# 08_FPGA_banks_6_7_8.net
KiCad netlist of a schematic drawn in Altium Designer
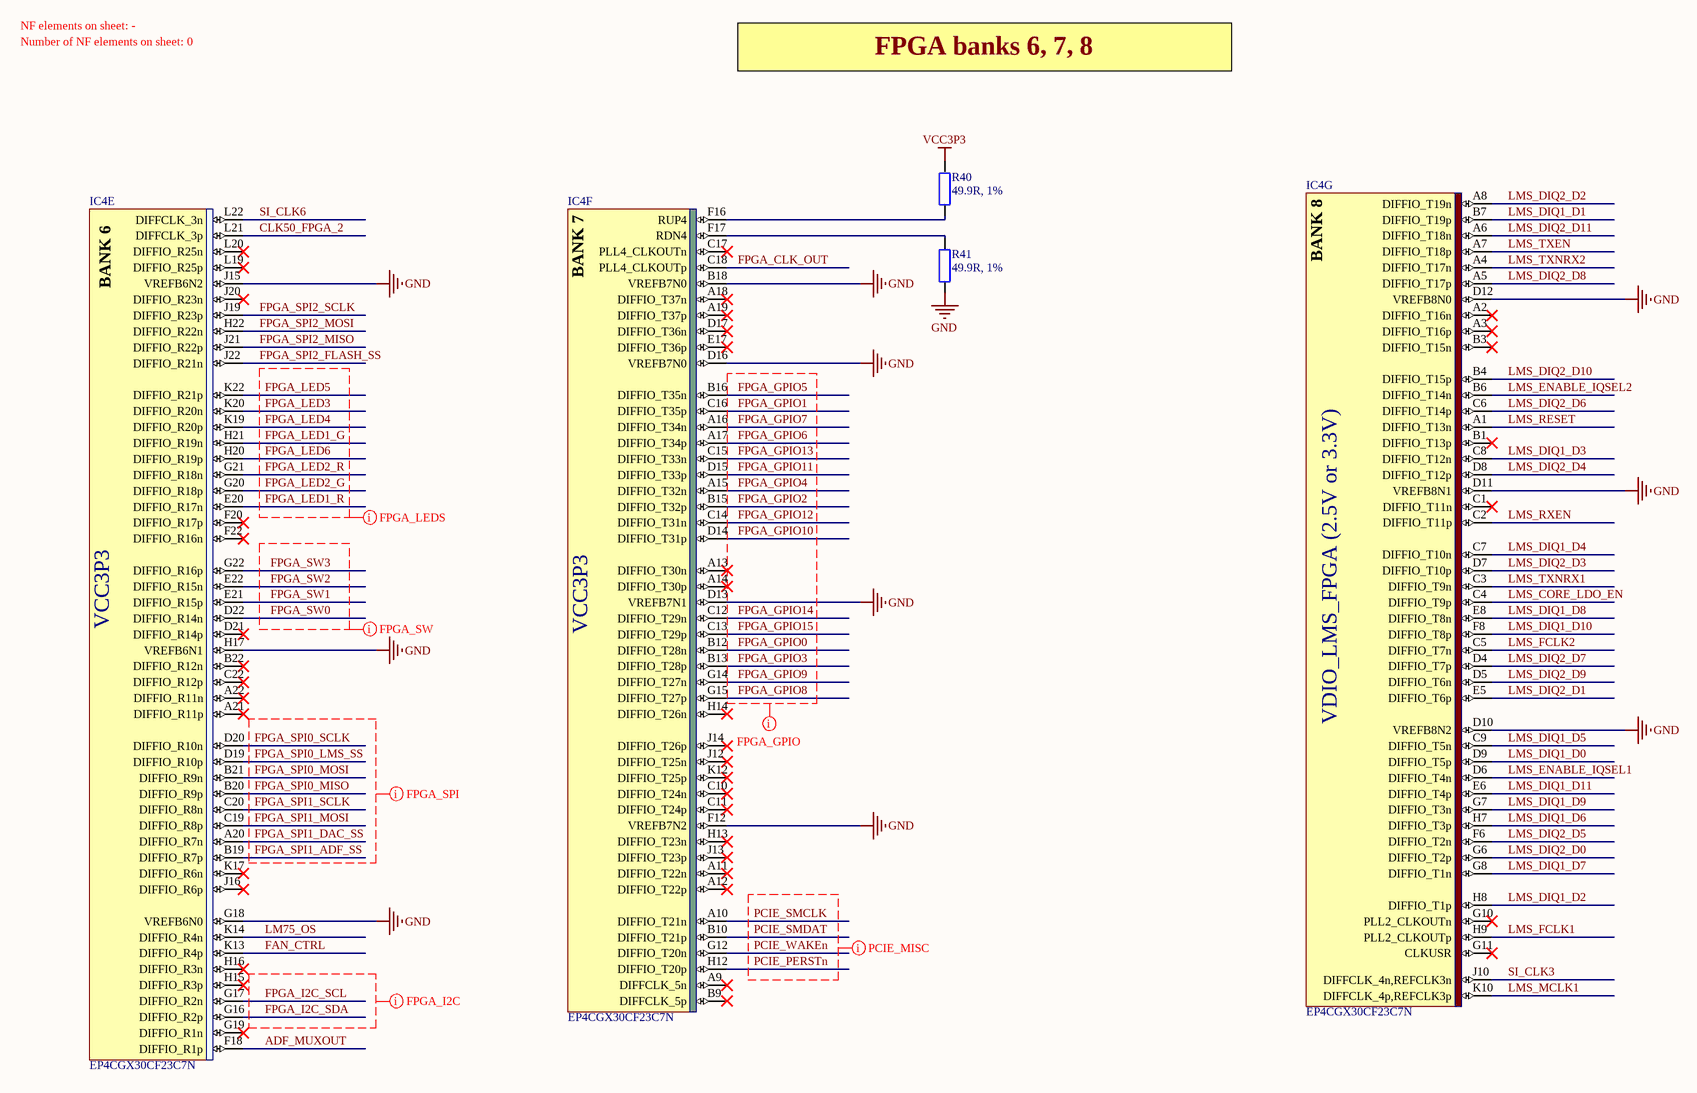
[diagram p0: 08_FPGA_banks_6_7_8.SchDoc]

(export (version "E")
  (design (tool "Eeschema 10.0.6"))
  (components
    (comp (ref "IC4")
      (value "EP4CGX30CF23C7N")
      (footprint "LimeMicroAltiumLib_pcbLib:ALTR-FBGA484_A-200")
      (fields (field (name "MANUFACTURER") "Altera"))
      (libsource (lib "LimeMicroAltiumLib_schLib") (part "EP4CGX30CF23C7N"))
    )
    (comp (ref "R40")
      (value "49.9R, 1%")
      (footprint "LimeMicroAltiumLib_pcbLib:RES0402")
      (fields
        (field (name "TOLERANCE") "±1%")
        (field (name "MANUFACTURER") "Samsung Electro-Mechanics America, Inc.")
        (field (name "MANUFACTURER PART NUMBER") "RC1005F49R9CS")
      )
      (libsource (lib "LimeMicroAltiumLib_schLib") (part "Res_0402"))
    )
    (comp (ref "R41")
      (value "49.9R, 1%")
      (footprint "LimeMicroAltiumLib_pcbLib:RES0402")
      (fields
        (field (name "TOLERANCE") "±1%")
        (field (name "MANUFACTURER") "Samsung Electro-Mechanics America, Inc.")
        (field (name "MANUFACTURER PART NUMBER") "RC1005F49R9CS")
      )
      (libsource (lib "LimeMicroAltiumLib_schLib") (part "Res_0402"))
    )
  )
  (nets
    (net (code "1") (name "/ADF_MUXOUT") (class "Default")
      (node (ref "IC4") (pin "F18") (pinfunction "DIFFIO_R1p_F18") (pintype "bidirectional"))
    )
    (net (code "2") (name "/CLK50_FPGA_2") (class "Default")
      (node (ref "IC4") (pin "L21") (pinfunction "DIFFCLK_3p_L21") (pintype "bidirectional"))
    )
    (net (code "3") (name "/FAN_CTRL") (class "Default")
      (node (ref "IC4") (pin "K13") (pinfunction "DIFFIO_R4p_K13") (pintype "bidirectional"))
    )
    (net (code "4") (name "/FPGA_CLK_OUT") (class "Default")
      (node (ref "IC4") (pin "C18") (pinfunction "PLL4_CLKOUTp_C18") (pintype "bidirectional"))
    )
    (net (code "5") (name "/FPGA_GPIO0") (class "Default")
      (node (ref "IC4") (pin "B12") (pinfunction "DIFFIO_T28n_B12") (pintype "bidirectional"))
    )
    (net (code "6") (name "/FPGA_GPIO1") (class "Default")
      (node (ref "IC4") (pin "C16") (pinfunction "DIFFIO_T35p_C16") (pintype "bidirectional"))
    )
    (net (code "7") (name "/FPGA_GPIO2") (class "Default")
      (node (ref "IC4") (pin "B15") (pinfunction "DIFFIO_T32p_B15") (pintype "bidirectional"))
    )
    (net (code "8") (name "/FPGA_GPIO3") (class "Default")
      (node (ref "IC4") (pin "B13") (pinfunction "DIFFIO_T28p_B13") (pintype "bidirectional"))
    )
    (net (code "9") (name "/FPGA_GPIO4") (class "Default")
      (node (ref "IC4") (pin "A15") (pinfunction "DIFFIO_T32n_A15") (pintype "bidirectional"))
    )
    (net (code "10") (name "/FPGA_GPIO5") (class "Default")
      (node (ref "IC4") (pin "B16") (pinfunction "DIFFIO_T35n_B16") (pintype "bidirectional"))
    )
    (net (code "11") (name "/FPGA_GPIO6") (class "Default")
      (node (ref "IC4") (pin "A17") (pinfunction "DIFFIO_T34p_A17") (pintype "bidirectional"))
    )
    (net (code "12") (name "/FPGA_GPIO7") (class "Default")
      (node (ref "IC4") (pin "A16") (pinfunction "DIFFIO_T34n_A16") (pintype "bidirectional"))
    )
    (net (code "13") (name "/FPGA_GPIO8") (class "Default")
      (node (ref "IC4") (pin "G15") (pinfunction "DIFFIO_T27p_G15") (pintype "bidirectional"))
    )
    (net (code "14") (name "/FPGA_GPIO9") (class "Default")
      (node (ref "IC4") (pin "G14") (pinfunction "DIFFIO_T27n_G14") (pintype "bidirectional"))
    )
    (net (code "15") (name "/FPGA_GPIO10") (class "Default")
      (node (ref "IC4") (pin "D14") (pinfunction "DIFFIO_T31p_D14") (pintype "bidirectional"))
    )
    (net (code "16") (name "/FPGA_GPIO11") (class "Default")
      (node (ref "IC4") (pin "D15") (pinfunction "DIFFIO_T33p_D15") (pintype "bidirectional"))
    )
    (net (code "17") (name "/FPGA_GPIO12") (class "Default")
      (node (ref "IC4") (pin "C14") (pinfunction "DIFFIO_T31n_C14") (pintype "bidirectional"))
    )
    (net (code "18") (name "/FPGA_GPIO13") (class "Default")
      (node (ref "IC4") (pin "C15") (pinfunction "DIFFIO_T33n_C15") (pintype "bidirectional"))
    )
    (net (code "19") (name "/FPGA_GPIO14") (class "Default")
      (node (ref "IC4") (pin "C12") (pinfunction "DIFFIO_T29n_C12") (pintype "bidirectional"))
    )
    (net (code "20") (name "/FPGA_GPIO15") (class "Default")
      (node (ref "IC4") (pin "C13") (pinfunction "DIFFIO_T29p_C13") (pintype "bidirectional"))
    )
    (net (code "21") (name "/FPGA_I2C_SCL") (class "Default")
      (node (ref "IC4") (pin "G17") (pinfunction "DIFFIO_R2n_G17") (pintype "bidirectional"))
    )
    (net (code "22") (name "/FPGA_I2C_SDA") (class "Default")
      (node (ref "IC4") (pin "G16") (pinfunction "DIFFIO_R2p_G16") (pintype "bidirectional"))
    )
    (net (code "23") (name "/FPGA_LED1_G") (class "Default")
      (node (ref "IC4") (pin "H21") (pinfunction "DIFFIO_R19n_H21") (pintype "bidirectional"))
    )
    (net (code "24") (name "/FPGA_LED1_R") (class "Default")
      (node (ref "IC4") (pin "E20") (pinfunction "DIFFIO_R17n_E20") (pintype "bidirectional"))
    )
    (net (code "25") (name "/FPGA_LED2_G") (class "Default")
      (node (ref "IC4") (pin "G20") (pinfunction "DIFFIO_R18p_G20") (pintype "bidirectional"))
    )
    (net (code "26") (name "/FPGA_LED2_R") (class "Default")
      (node (ref "IC4") (pin "G21") (pinfunction "DIFFIO_R18n_G21") (pintype "bidirectional"))
    )
    (net (code "27") (name "/FPGA_LED3") (class "Default")
      (node (ref "IC4") (pin "K20") (pinfunction "DIFFIO_R20n_K20") (pintype "bidirectional"))
    )
    (net (code "28") (name "/FPGA_LED4") (class "Default")
      (node (ref "IC4") (pin "K19") (pinfunction "DIFFIO_R20p_K19") (pintype "bidirectional"))
    )
    (net (code "29") (name "/FPGA_LED5") (class "Default")
      (node (ref "IC4") (pin "K22") (pinfunction "DIFFIO_R21p_K22") (pintype "bidirectional"))
    )
    (net (code "30") (name "/FPGA_LED6") (class "Default")
      (node (ref "IC4") (pin "H20") (pinfunction "DIFFIO_R19p_H20") (pintype "bidirectional"))
    )
    (net (code "31") (name "/FPGA_SPI0_LMS_SS") (class "Default")
      (node (ref "IC4") (pin "D19") (pinfunction "DIFFIO_R10p_D19") (pintype "bidirectional"))
    )
    (net (code "32") (name "/FPGA_SPI0_MISO") (class "Default")
      (node (ref "IC4") (pin "B20") (pinfunction "DIFFIO_R9p_B20") (pintype "bidirectional"))
    )
    (net (code "33") (name "/FPGA_SPI0_MOSI") (class "Default")
      (node (ref "IC4") (pin "B21") (pinfunction "DIFFIO_R9n_B21") (pintype "bidirectional"))
    )
    (net (code "34") (name "/FPGA_SPI0_SCLK") (class "Default")
      (node (ref "IC4") (pin "D20") (pinfunction "DIFFIO_R10n_D20") (pintype "bidirectional"))
    )
    (net (code "35") (name "/FPGA_SPI1_ADF_SS") (class "Default")
      (node (ref "IC4") (pin "B19") (pinfunction "DIFFIO_R7p_B19") (pintype "bidirectional"))
    )
    (net (code "36") (name "/FPGA_SPI1_DAC_SS") (class "Default")
      (node (ref "IC4") (pin "A20") (pinfunction "DIFFIO_R7n_A20") (pintype "bidirectional"))
    )
    (net (code "37") (name "/FPGA_SPI1_MOSI") (class "Default")
      (node (ref "IC4") (pin "C19") (pinfunction "DIFFIO_R8p_C19") (pintype "bidirectional"))
    )
    (net (code "38") (name "/FPGA_SPI1_SCLK") (class "Default")
      (node (ref "IC4") (pin "C20") (pinfunction "DIFFIO_R8n_C20") (pintype "bidirectional"))
    )
    (net (code "39") (name "/FPGA_SPI2_FLASH_SS") (class "Default")
      (node (ref "IC4") (pin "J22") (pinfunction "DIFFIO_R21n_J22") (pintype "bidirectional"))
    )
    (net (code "40") (name "/FPGA_SPI2_MISO") (class "Default")
      (node (ref "IC4") (pin "J21") (pinfunction "DIFFIO_R22p_J21") (pintype "bidirectional"))
    )
    (net (code "41") (name "/FPGA_SPI2_MOSI") (class "Default")
      (node (ref "IC4") (pin "H22") (pinfunction "DIFFIO_R22n_H22") (pintype "bidirectional"))
    )
    (net (code "42") (name "/FPGA_SPI2_SCLK") (class "Default")
      (node (ref "IC4") (pin "J19") (pinfunction "DIFFIO_R23p_J19") (pintype "bidirectional"))
    )
    (net (code "43") (name "/FPGA_SW0") (class "Default")
      (node (ref "IC4") (pin "D22") (pinfunction "DIFFIO_R14n_D22") (pintype "bidirectional"))
    )
    (net (code "44") (name "/FPGA_SW1") (class "Default")
      (node (ref "IC4") (pin "E21") (pinfunction "DIFFIO_R15p_E21") (pintype "bidirectional"))
    )
    (net (code "45") (name "/FPGA_SW2") (class "Default")
      (node (ref "IC4") (pin "E22") (pinfunction "DIFFIO_R15n_E22") (pintype "bidirectional"))
    )
    (net (code "46") (name "/FPGA_SW3") (class "Default")
      (node (ref "IC4") (pin "G22") (pinfunction "DIFFIO_R16p_G22") (pintype "bidirectional"))
    )
    (net (code "47") (name "/LM75_OS") (class "Default")
      (node (ref "IC4") (pin "K14") (pinfunction "DIFFIO_R4n_K14") (pintype "bidirectional"))
    )
    (net (code "48") (name "/LMS_CORE_LDO_EN") (class "Default")
      (node (ref "IC4") (pin "C4") (pinfunction "DIFFIO_T9p_C4") (pintype "bidirectional"))
    )
    (net (code "49") (name "/LMS_DIQ1_D0") (class "Default")
      (node (ref "IC4") (pin "D9") (pinfunction "DIFFIO_T5p_D9") (pintype "bidirectional"))
    )
    (net (code "50") (name "/LMS_DIQ1_D1") (class "Default")
      (node (ref "IC4") (pin "B7") (pinfunction "DIFFIO_T19p_B7") (pintype "bidirectional"))
    )
    (net (code "51") (name "/LMS_DIQ1_D2") (class "Default")
      (node (ref "IC4") (pin "H8") (pinfunction "DIFFIO_T1p_H8") (pintype "bidirectional"))
    )
    (net (code "52") (name "/LMS_DIQ1_D3") (class "Default")
      (node (ref "IC4") (pin "C8") (pinfunction "DIFFIO_T12n_C8") (pintype "bidirectional"))
    )
    (net (code "53") (name "/LMS_DIQ1_D4") (class "Default")
      (node (ref "IC4") (pin "C7") (pinfunction "DIFFIO_T10n_C7") (pintype "bidirectional"))
    )
    (net (code "54") (name "/LMS_DIQ1_D5") (class "Default")
      (node (ref "IC4") (pin "C9") (pinfunction "DIFFIO_T5n_C9") (pintype "bidirectional"))
    )
    (net (code "55") (name "/LMS_DIQ1_D6") (class "Default")
      (node (ref "IC4") (pin "H7") (pinfunction "DIFFIO_T3p_H7") (pintype "bidirectional"))
    )
    (net (code "56") (name "/LMS_DIQ1_D7") (class "Default")
      (node (ref "IC4") (pin "G8") (pinfunction "DIFFIO_T1n_G8") (pintype "bidirectional"))
    )
    (net (code "57") (name "/LMS_DIQ1_D8") (class "Default")
      (node (ref "IC4") (pin "E8") (pinfunction "DIFFIO_T8n_E8") (pintype "bidirectional"))
    )
    (net (code "58") (name "/LMS_DIQ1_D9") (class "Default")
      (node (ref "IC4") (pin "G7") (pinfunction "DIFFIO_T3n_G7") (pintype "bidirectional"))
    )
    (net (code "59") (name "/LMS_DIQ1_D10") (class "Default")
      (node (ref "IC4") (pin "F8") (pinfunction "DIFFIO_T8p_F8") (pintype "bidirectional"))
    )
    (net (code "60") (name "/LMS_DIQ1_D11") (class "Default")
      (node (ref "IC4") (pin "E6") (pinfunction "DIFFIO_T4p_E6") (pintype "bidirectional"))
    )
    (net (code "61") (name "/LMS_DIQ2_D0") (class "Default")
      (node (ref "IC4") (pin "G6") (pinfunction "DIFFIO_T2p_G6") (pintype "bidirectional"))
    )
    (net (code "62") (name "/LMS_DIQ2_D1") (class "Default")
      (node (ref "IC4") (pin "E5") (pinfunction "DIFFIO_T6p_E5") (pintype "bidirectional"))
    )
    (net (code "63") (name "/LMS_DIQ2_D2") (class "Default")
      (node (ref "IC4") (pin "A8") (pinfunction "DIFFIO_T19n_A8") (pintype "bidirectional"))
    )
    (net (code "64") (name "/LMS_DIQ2_D3") (class "Default")
      (node (ref "IC4") (pin "D7") (pinfunction "DIFFIO_T10p_D7") (pintype "bidirectional"))
    )
    (net (code "65") (name "/LMS_DIQ2_D4") (class "Default")
      (node (ref "IC4") (pin "D8") (pinfunction "DIFFIO_T12p_D8") (pintype "bidirectional"))
    )
    (net (code "66") (name "/LMS_DIQ2_D5") (class "Default")
      (node (ref "IC4") (pin "F6") (pinfunction "DIFFIO_T2n_F6") (pintype "bidirectional"))
    )
    (net (code "67") (name "/LMS_DIQ2_D6") (class "Default")
      (node (ref "IC4") (pin "C6") (pinfunction "DIFFIO_T14p_C6") (pintype "bidirectional"))
    )
    (net (code "68") (name "/LMS_DIQ2_D7") (class "Default")
      (node (ref "IC4") (pin "D4") (pinfunction "DIFFIO_T7p_D4") (pintype "bidirectional"))
    )
    (net (code "69") (name "/LMS_DIQ2_D8") (class "Default")
      (node (ref "IC4") (pin "A5") (pinfunction "DIFFIO_T17p_A5") (pintype "bidirectional"))
    )
    (net (code "70") (name "/LMS_DIQ2_D9") (class "Default")
      (node (ref "IC4") (pin "D5") (pinfunction "DIFFIO_T6n_D5") (pintype "bidirectional"))
    )
    (net (code "71") (name "/LMS_DIQ2_D10") (class "Default")
      (node (ref "IC4") (pin "B4") (pinfunction "DIFFIO_T15p_B4") (pintype "bidirectional"))
    )
    (net (code "72") (name "/LMS_DIQ2_D11") (class "Default")
      (node (ref "IC4") (pin "A6") (pinfunction "DIFFIO_T18n_A6") (pintype "bidirectional"))
    )
    (net (code "73") (name "/LMS_ENABLE_IQSEL1") (class "Default")
      (node (ref "IC4") (pin "D6") (pinfunction "DIFFIO_T4n_D6") (pintype "bidirectional"))
    )
    (net (code "74") (name "/LMS_ENABLE_IQSEL2") (class "Default")
      (node (ref "IC4") (pin "B6") (pinfunction "DIFFIO_T14n_B6") (pintype "bidirectional"))
    )
    (net (code "75") (name "/LMS_FCLK1") (class "Default")
      (node (ref "IC4") (pin "H9") (pinfunction "PLL2_CLKOUTp_H9") (pintype "bidirectional"))
    )
    (net (code "76") (name "/LMS_FCLK2") (class "Default")
      (node (ref "IC4") (pin "C5") (pinfunction "DIFFIO_T7n_C5") (pintype "bidirectional"))
    )
    (net (code "77") (name "/LMS_MCLK1") (class "Default")
      (node (ref "IC4") (pin "K10") (pinfunction "DIFFCLK_4p,REFCLK3p_K10") (pintype "bidirectional"))
    )
    (net (code "78") (name "/LMS_RESET") (class "Default")
      (node (ref "IC4") (pin "A1") (pinfunction "DIFFIO_T13n_A1") (pintype "bidirectional"))
    )
    (net (code "79") (name "/LMS_RXEN") (class "Default")
      (node (ref "IC4") (pin "C2") (pinfunction "DIFFIO_T11p_C2") (pintype "bidirectional"))
    )
    (net (code "80") (name "/LMS_TXEN") (class "Default")
      (node (ref "IC4") (pin "A7") (pinfunction "DIFFIO_T18p_A7") (pintype "bidirectional"))
    )
    (net (code "81") (name "/LMS_TXNRX1") (class "Default")
      (node (ref "IC4") (pin "C3") (pinfunction "DIFFIO_T9n_C3") (pintype "bidirectional"))
    )
    (net (code "82") (name "/LMS_TXNRX2") (class "Default")
      (node (ref "IC4") (pin "A4") (pinfunction "DIFFIO_T17n_A4") (pintype "bidirectional"))
    )
    (net (code "83") (name "/PCIE_PERSTn") (class "Default")
      (node (ref "IC4") (pin "H12") (pinfunction "DIFFIO_T20p_H12") (pintype "bidirectional"))
    )
    (net (code "84") (name "/PCIE_SMCLK") (class "Default")
      (node (ref "IC4") (pin "A10") (pinfunction "DIFFIO_T21n_A10") (pintype "bidirectional"))
    )
    (net (code "85") (name "/PCIE_SMDAT") (class "Default")
      (node (ref "IC4") (pin "B10") (pinfunction "DIFFIO_T21p_B10") (pintype "bidirectional"))
    )
    (net (code "86") (name "/PCIE_WAKEn") (class "Default")
      (node (ref "IC4") (pin "G12") (pinfunction "DIFFIO_T20n_G12") (pintype "bidirectional"))
    )
    (net (code "87") (name "/SI_CLK3") (class "Default")
      (node (ref "IC4") (pin "J10") (pinfunction "DIFFCLK_4n,REFCLK3n_J10") (pintype "bidirectional"))
    )
    (net (code "88") (name "/SI_CLK6") (class "Default")
      (node (ref "IC4") (pin "L22") (pinfunction "DIFFCLK_3n_L22") (pintype "bidirectional"))
    )
    (net (code "89") (name "GND") (class "Default")
      (node (ref "IC4") (pin "B18") (pinfunction "VREFB7N0_B18") (pintype "bidirectional"))
      (node (ref "IC4") (pin "D10") (pinfunction "VREFB8N2_D10") (pintype "bidirectional"))
      (node (ref "IC4") (pin "D11") (pinfunction "VREFB8N1_D11") (pintype "bidirectional"))
      (node (ref "IC4") (pin "D12") (pinfunction "VREFB8N0_D12") (pintype "bidirectional"))
      (node (ref "IC4") (pin "D13") (pinfunction "VREFB7N1_D13") (pintype "bidirectional"))
      (node (ref "IC4") (pin "D16") (pinfunction "VREFB7N0_D16") (pintype "bidirectional"))
      (node (ref "IC4") (pin "F12") (pinfunction "VREFB7N2_F12") (pintype "bidirectional"))
      (node (ref "IC4") (pin "G18") (pinfunction "VREFB6N0_G18") (pintype "bidirectional"))
      (node (ref "IC4") (pin "H17") (pinfunction "VREFB6N1_H17") (pintype "bidirectional"))
      (node (ref "IC4") (pin "J15") (pinfunction "VREFB6N2_J15") (pintype "bidirectional"))
      (node (ref "R41") (pin "1") (pinfunction "1_1") (pintype "passive"))
    )
    (net (code "90") (name "Net-(IC4F-RDN4)") (class "Default")
      (node (ref "IC4") (pin "F17") (pinfunction "RDN4_F17") (pintype "bidirectional"))
      (node (ref "R41") (pin "2") (pinfunction "2_2") (pintype "passive"))
    )
    (net (code "91") (name "Net-(IC4F-RUP4)") (class "Default")
      (node (ref "IC4") (pin "F16") (pinfunction "RUP4_F16") (pintype "bidirectional"))
      (node (ref "R40") (pin "1") (pinfunction "1_1") (pintype "passive"))
    )
    (net (code "92") (name "VCC3P3") (class "Default")
      (node (ref "R40") (pin "2") (pinfunction "2_2") (pintype "passive"))
    )
    (net (code "93") (name "unconnected-(IC4E-DIFFIO_R1n-PadG19)") (class "Default")
      (node (ref "IC4") (pin "G19") (pinfunction "DIFFIO_R1n_G19") (pintype "bidirectional+no_connect"))
    )
    (net (code "94") (name "unconnected-(IC4E-DIFFIO_R3n-PadH16)") (class "Default")
      (node (ref "IC4") (pin "H16") (pinfunction "DIFFIO_R3n_H16") (pintype "bidirectional+no_connect"))
    )
    (net (code "95") (name "unconnected-(IC4E-DIFFIO_R3p-PadH15)") (class "Default")
      (node (ref "IC4") (pin "H15") (pinfunction "DIFFIO_R3p_H15") (pintype "bidirectional+no_connect"))
    )
    (net (code "96") (name "unconnected-(IC4E-DIFFIO_R6n-PadK17)") (class "Default")
      (node (ref "IC4") (pin "K17") (pinfunction "DIFFIO_R6n_K17") (pintype "bidirectional+no_connect"))
    )
    (net (code "97") (name "unconnected-(IC4E-DIFFIO_R6p-PadJ16)") (class "Default")
      (node (ref "IC4") (pin "J16") (pinfunction "DIFFIO_R6p_J16") (pintype "bidirectional+no_connect"))
    )
    (net (code "98") (name "unconnected-(IC4E-DIFFIO_R11n-PadA22)") (class "Default")
      (node (ref "IC4") (pin "A22") (pinfunction "DIFFIO_R11n_A22") (pintype "bidirectional+no_connect"))
    )
    (net (code "99") (name "unconnected-(IC4E-DIFFIO_R11p-PadA21)") (class "Default")
      (node (ref "IC4") (pin "A21") (pinfunction "DIFFIO_R11p_A21") (pintype "bidirectional+no_connect"))
    )
    (net (code "100") (name "unconnected-(IC4E-DIFFIO_R12n-PadB22)") (class "Default")
      (node (ref "IC4") (pin "B22") (pinfunction "DIFFIO_R12n_B22") (pintype "bidirectional+no_connect"))
    )
    (net (code "101") (name "unconnected-(IC4E-DIFFIO_R12p-PadC22)") (class "Default")
      (node (ref "IC4") (pin "C22") (pinfunction "DIFFIO_R12p_C22") (pintype "bidirectional+no_connect"))
    )
    (net (code "102") (name "unconnected-(IC4E-DIFFIO_R14p-PadD21)") (class "Default")
      (node (ref "IC4") (pin "D21") (pinfunction "DIFFIO_R14p_D21") (pintype "bidirectional+no_connect"))
    )
    (net (code "103") (name "unconnected-(IC4E-DIFFIO_R16n-PadF22)") (class "Default")
      (node (ref "IC4") (pin "F22") (pinfunction "DIFFIO_R16n_F22") (pintype "bidirectional+no_connect"))
    )
    (net (code "104") (name "unconnected-(IC4E-DIFFIO_R17p-PadF20)") (class "Default")
      (node (ref "IC4") (pin "F20") (pinfunction "DIFFIO_R17p_F20") (pintype "bidirectional+no_connect"))
    )
    (net (code "105") (name "unconnected-(IC4E-DIFFIO_R23n-PadJ20)") (class "Default")
      (node (ref "IC4") (pin "J20") (pinfunction "DIFFIO_R23n_J20") (pintype "bidirectional+no_connect"))
    )
    (net (code "106") (name "unconnected-(IC4E-DIFFIO_R25n-PadL20)") (class "Default")
      (node (ref "IC4") (pin "L20") (pinfunction "DIFFIO_R25n_L20") (pintype "bidirectional+no_connect"))
    )
    (net (code "107") (name "unconnected-(IC4E-DIFFIO_R25p-PadL19)") (class "Default")
      (node (ref "IC4") (pin "L19") (pinfunction "DIFFIO_R25p_L19") (pintype "bidirectional+no_connect"))
    )
    (net (code "108") (name "unconnected-(IC4F-DIFFCLK_5n-PadA9)") (class "Default")
      (node (ref "IC4") (pin "A9") (pinfunction "DIFFCLK_5n_A9") (pintype "bidirectional+no_connect"))
    )
    (net (code "109") (name "unconnected-(IC4F-DIFFCLK_5p-PadB9)") (class "Default")
      (node (ref "IC4") (pin "B9") (pinfunction "DIFFCLK_5p_B9") (pintype "bidirectional+no_connect"))
    )
    (net (code "110") (name "unconnected-(IC4F-DIFFIO_T22n-PadA11)") (class "Default")
      (node (ref "IC4") (pin "A11") (pinfunction "DIFFIO_T22n_A11") (pintype "bidirectional+no_connect"))
    )
    (net (code "111") (name "unconnected-(IC4F-DIFFIO_T22p-PadA12)") (class "Default")
      (node (ref "IC4") (pin "A12") (pinfunction "DIFFIO_T22p_A12") (pintype "bidirectional+no_connect"))
    )
    (net (code "112") (name "unconnected-(IC4F-DIFFIO_T23n-PadH13)") (class "Default")
      (node (ref "IC4") (pin "H13") (pinfunction "DIFFIO_T23n_H13") (pintype "bidirectional+no_connect"))
    )
    (net (code "113") (name "unconnected-(IC4F-DIFFIO_T23p-PadJ13)") (class "Default")
      (node (ref "IC4") (pin "J13") (pinfunction "DIFFIO_T23p_J13") (pintype "bidirectional+no_connect"))
    )
    (net (code "114") (name "unconnected-(IC4F-DIFFIO_T24n-PadC10)") (class "Default")
      (node (ref "IC4") (pin "C10") (pinfunction "DIFFIO_T24n_C10") (pintype "bidirectional+no_connect"))
    )
    (net (code "115") (name "unconnected-(IC4F-DIFFIO_T24p-PadC11)") (class "Default")
      (node (ref "IC4") (pin "C11") (pinfunction "DIFFIO_T24p_C11") (pintype "bidirectional+no_connect"))
    )
    (net (code "116") (name "unconnected-(IC4F-DIFFIO_T25n-PadJ12)") (class "Default")
      (node (ref "IC4") (pin "J12") (pinfunction "DIFFIO_T25n_J12") (pintype "bidirectional+no_connect"))
    )
    (net (code "117") (name "unconnected-(IC4F-DIFFIO_T25p-PadK12)") (class "Default")
      (node (ref "IC4") (pin "K12") (pinfunction "DIFFIO_T25p_K12") (pintype "bidirectional+no_connect"))
    )
    (net (code "118") (name "unconnected-(IC4F-DIFFIO_T26n-PadH14)") (class "Default")
      (node (ref "IC4") (pin "H14") (pinfunction "DIFFIO_T26n_H14") (pintype "bidirectional+no_connect"))
    )
    (net (code "119") (name "unconnected-(IC4F-DIFFIO_T26p-PadJ14)") (class "Default")
      (node (ref "IC4") (pin "J14") (pinfunction "DIFFIO_T26p_J14") (pintype "bidirectional+no_connect"))
    )
    (net (code "120") (name "unconnected-(IC4F-DIFFIO_T30n-PadA13)") (class "Default")
      (node (ref "IC4") (pin "A13") (pinfunction "DIFFIO_T30n_A13") (pintype "bidirectional+no_connect"))
    )
    (net (code "121") (name "unconnected-(IC4F-DIFFIO_T30p-PadA14)") (class "Default")
      (node (ref "IC4") (pin "A14") (pinfunction "DIFFIO_T30p_A14") (pintype "bidirectional+no_connect"))
    )
    (net (code "122") (name "unconnected-(IC4F-DIFFIO_T36n-PadD17)") (class "Default")
      (node (ref "IC4") (pin "D17") (pinfunction "DIFFIO_T36n_D17") (pintype "bidirectional+no_connect"))
    )
    (net (code "123") (name "unconnected-(IC4F-DIFFIO_T36p-PadE17)") (class "Default")
      (node (ref "IC4") (pin "E17") (pinfunction "DIFFIO_T36p_E17") (pintype "bidirectional+no_connect"))
    )
    (net (code "124") (name "unconnected-(IC4F-DIFFIO_T37n-PadA18)") (class "Default")
      (node (ref "IC4") (pin "A18") (pinfunction "DIFFIO_T37n_A18") (pintype "bidirectional+no_connect"))
    )
    (net (code "125") (name "unconnected-(IC4F-DIFFIO_T37p-PadA19)") (class "Default")
      (node (ref "IC4") (pin "A19") (pinfunction "DIFFIO_T37p_A19") (pintype "bidirectional+no_connect"))
    )
    (net (code "126") (name "unconnected-(IC4F-PLL4_CLKOUTn-PadC17)") (class "Default")
      (node (ref "IC4") (pin "C17") (pinfunction "PLL4_CLKOUTn_C17") (pintype "bidirectional+no_connect"))
    )
    (net (code "127") (name "unconnected-(IC4G-CLKUSR-PadG11)") (class "Default")
      (node (ref "IC4") (pin "G11") (pinfunction "CLKUSR_G11") (pintype "bidirectional+no_connect"))
    )
    (net (code "128") (name "unconnected-(IC4G-DIFFIO_T11n-PadC1)") (class "Default")
      (node (ref "IC4") (pin "C1") (pinfunction "DIFFIO_T11n_C1") (pintype "bidirectional+no_connect"))
    )
    (net (code "129") (name "unconnected-(IC4G-DIFFIO_T13p-PadB1)") (class "Default")
      (node (ref "IC4") (pin "B1") (pinfunction "DIFFIO_T13p_B1") (pintype "bidirectional+no_connect"))
    )
    (net (code "130") (name "unconnected-(IC4G-DIFFIO_T15n-PadB3)") (class "Default")
      (node (ref "IC4") (pin "B3") (pinfunction "DIFFIO_T15n_B3") (pintype "bidirectional+no_connect"))
    )
    (net (code "131") (name "unconnected-(IC4G-DIFFIO_T16n-PadA2)") (class "Default")
      (node (ref "IC4") (pin "A2") (pinfunction "DIFFIO_T16n_A2") (pintype "bidirectional+no_connect"))
    )
    (net (code "132") (name "unconnected-(IC4G-DIFFIO_T16p-PadA3)") (class "Default")
      (node (ref "IC4") (pin "A3") (pinfunction "DIFFIO_T16p_A3") (pintype "bidirectional+no_connect"))
    )
    (net (code "133") (name "unconnected-(IC4G-PLL2_CLKOUTn-PadG10)") (class "Default")
      (node (ref "IC4") (pin "G10") (pinfunction "PLL2_CLKOUTn_G10") (pintype "bidirectional+no_connect"))
    )
  )
)
